# voltage_adj_current_source.net
KiCad netlist of a schematic drawn in Altium Designer
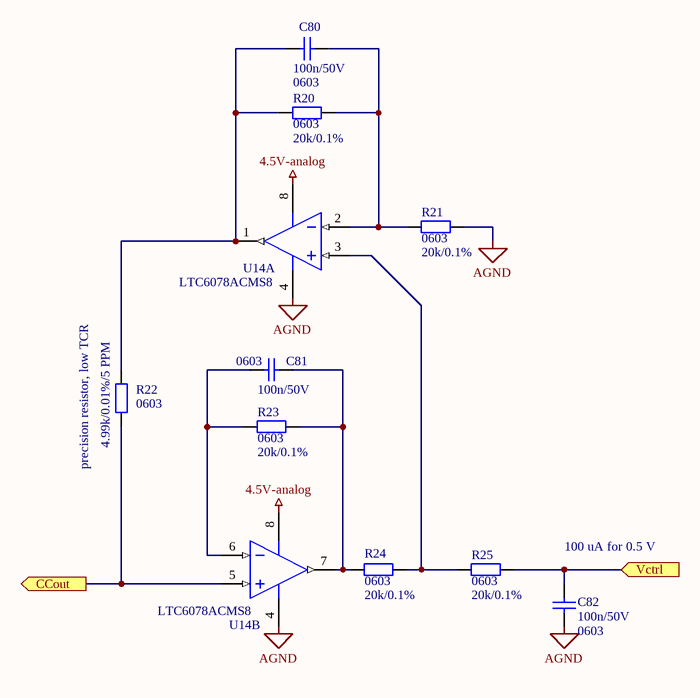
[diagram p0: voltage_adj_current_source.SchDoc]

(export (version "E")
  (design (tool "Eeschema 10.0.6"))
  (components
    (comp (ref "C80")
      (value "100n/50V")
      (footprint "SMD_Capacitor_0603")
      (description "Ceramic Cap Kemet COTS 100n/50V X7R 0603")
      (fields
        (field (name "MANUFACTURER") "Kemet")
        (field (name "MANUFACTURERPARTNUMBER") "C0603T104K5RALTU")
        (field (name "PACKAGE") "0603")
      )
      (libsource (lib "capacitors") (part "Cer_C0603T104K5RALTU"))
    )
    (comp (ref "C81")
      (value "100n/50V")
      (footprint "SMD_Capacitor_0603")
      (description "Ceramic Cap Kemet COTS 100n/50V X7R 0603")
      (fields
        (field (name "MANUFACTURER") "Kemet")
        (field (name "MANUFACTURERPARTNUMBER") "C0603T104K5RALTU")
        (field (name "PACKAGE") "0603")
      )
      (libsource (lib "capacitors") (part "Cer_C0603T104K5RALTU"))
    )
    (comp (ref "C82")
      (value "100n/50V")
      (footprint "SMD_Capacitor_0603")
      (description "Ceramic Cap Kemet COTS 100n/50V X7R 0603")
      (fields
        (field (name "MANUFACTURER") "Kemet")
        (field (name "MANUFACTURERPARTNUMBER") "C0603T104K5RALTU")
        (field (name "PACKAGE") "0603")
      )
      (libsource (lib "capacitors") (part "Cer_C0603T104K5RALTU"))
    )
    (comp (ref "R20")
      (value "0603")
      (footprint "SMD_Resistor_0603")
      (description "Resistor")
      (fields (field (name "ALTIUM_VALUE") "20k/0.1%") (field (name "PUBLISHER") "Altium Limited"))
      (libsource (lib "Miscellaneous Devices") (part "Res2"))
    )
    (comp (ref "R21")
      (value "0603")
      (footprint "SMD_Resistor_0603")
      (description "Resistor")
      (fields (field (name "ALTIUM_VALUE") "20k/0.1%") (field (name "PUBLISHER") "Altium Limited"))
      (libsource (lib "Miscellaneous Devices") (part "Res2"))
    )
    (comp (ref "R22")
      (value "0603")
      (footprint "SMD_Resistor_0603")
      (description "Resistor")
      (fields (field (name "ALTIUM_VALUE") "4.99k/0.01%/5 PPM") (field (name "PUBLISHER") "Altium Limited"))
      (libsource (lib "") (part "Res2_1"))
    )
    (comp (ref "R23")
      (value "0603")
      (footprint "SMD_Resistor_0603")
      (description "Resistor")
      (fields (field (name "ALTIUM_VALUE") "20k/0.1%") (field (name "PUBLISHER") "Altium Limited"))
      (libsource (lib "Miscellaneous Devices") (part "Res2"))
    )
    (comp (ref "R24")
      (value "0603")
      (footprint "SMD_Resistor_0603")
      (description "Resistor")
      (fields (field (name "ALTIUM_VALUE") "20k/0.1%") (field (name "PUBLISHER") "Altium Limited"))
      (libsource (lib "Miscellaneous Devices") (part "Res2"))
    )
    (comp (ref "R25")
      (value "0603")
      (footprint "SMD_Resistor_0603")
      (description "Resistor")
      (fields (field (name "ALTIUM_VALUE") "20k/0.1%") (field (name "PUBLISHER") "Altium Limited"))
      (libsource (lib "Miscellaneous Devices") (part "Res2"))
    )
    (comp (ref "U14")
      (value "LTC6078ACMS8")
      (footprint "LT-MS8-8_N")
      (fields
        (field (name "LINEAR TECHNOLOGY PART NUMBER") "LTC6078")
        (field (name "MANUFACTURER") "Linear Technology")
      )
      (libsource (lib "Linear Technology Operational Amplifiers (LT2000-LT6000)") (part "LTC6078ACMS8"))
    )
  )
  (nets
    (net (code "1") (name "/CCout") (class "Default")
      (node (ref "R22") (pin "1") (pinfunction "1_1") (pintype "passive"))
      (node (ref "U14") (pin "5") (pinfunction "+INB_5") (pintype "input"))
    )
    (net (code "2") (name "/Vctrl") (class "Default")
      (node (ref "C82") (pin "2") (pinfunction "2_2") (pintype "passive"))
      (node (ref "R25") (pin "1") (pinfunction "1_1") (pintype "passive"))
    )
    (net (code "3") (name "4.5V-analog") (class "Default")
      (node (ref "U14") (pin "8") (pinfunction "V+_8") (pintype "power_in"))
    )
    (net (code "4") (name "AGND") (class "Default")
      (node (ref "C82") (pin "1") (pinfunction "1_1") (pintype "passive"))
      (node (ref "R21") (pin "1") (pinfunction "1_1") (pintype "passive"))
      (node (ref "U14") (pin "4") (pinfunction "V-_4") (pintype "power_in"))
    )
    (net (code "5") (name "Net-(U14A-+INA)") (class "Default")
      (node (ref "R24") (pin "1") (pinfunction "1_1") (pintype "passive"))
      (node (ref "R25") (pin "2") (pinfunction "2_2") (pintype "passive"))
      (node (ref "U14") (pin "3") (pinfunction "+INA_3") (pintype "input"))
    )
    (net (code "6") (name "Net-(U14A--INA)") (class "Default")
      (node (ref "C80") (pin "2") (pinfunction "2_2") (pintype "passive"))
      (node (ref "R20") (pin "1") (pinfunction "1_1") (pintype "passive"))
      (node (ref "R21") (pin "2") (pinfunction "2_2") (pintype "passive"))
      (node (ref "U14") (pin "2") (pinfunction "-INA_2") (pintype "input"))
    )
    (net (code "7") (name "Net-(U14A-OUTA)") (class "Default")
      (node (ref "C80") (pin "1") (pinfunction "1_1") (pintype "passive"))
      (node (ref "R20") (pin "2") (pinfunction "2_2") (pintype "passive"))
      (node (ref "R22") (pin "2") (pinfunction "2_2") (pintype "passive"))
      (node (ref "U14") (pin "1") (pinfunction "OUTA_1") (pintype "output"))
    )
    (net (code "8") (name "Net-(U14B--INB)") (class "Default")
      (node (ref "C81") (pin "1") (pinfunction "1_1") (pintype "passive"))
      (node (ref "R23") (pin "2") (pinfunction "2_2") (pintype "passive"))
      (node (ref "U14") (pin "6") (pinfunction "-INB_6") (pintype "input"))
    )
    (net (code "9") (name "Net-(U14B-OUTB)") (class "Default")
      (node (ref "C81") (pin "2") (pinfunction "2_2") (pintype "passive"))
      (node (ref "R23") (pin "1") (pinfunction "1_1") (pintype "passive"))
      (node (ref "R24") (pin "2") (pinfunction "2_2") (pintype "passive"))
      (node (ref "U14") (pin "7") (pinfunction "OUTB_7") (pintype "output"))
    )
  )
)
